# Microcontroller.net
KiCad netlist of a schematic drawn in Altium Designer
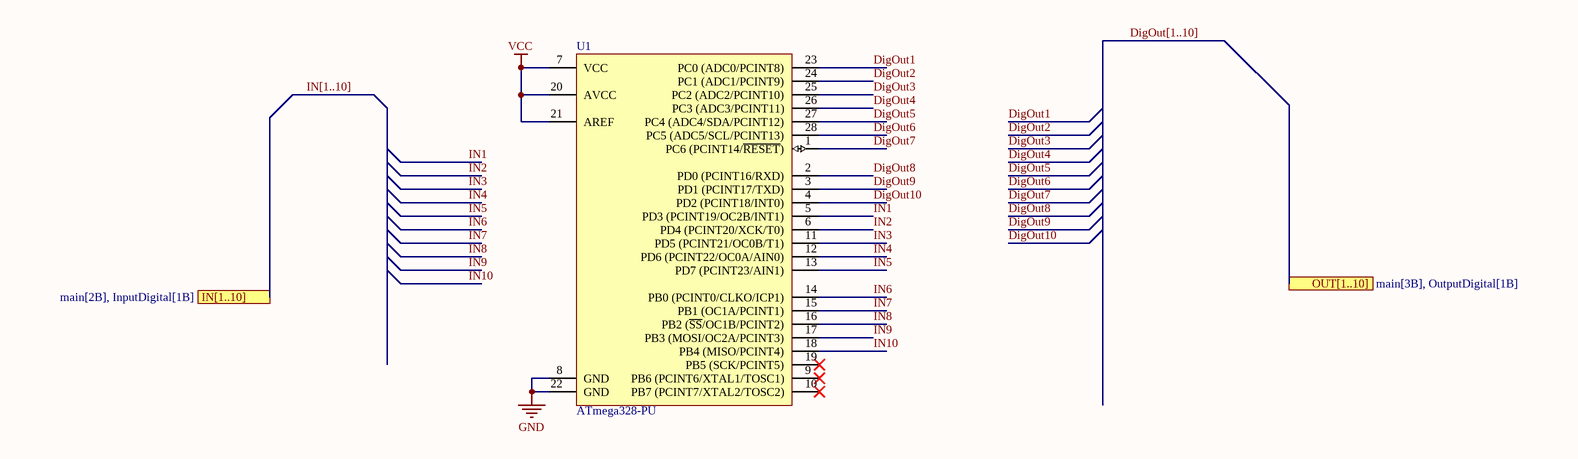
[diagram p0: Microcontroller.SchDoc]

(export (version "E")
  (design (tool "Eeschema 10.0.6"))
  (components
    (comp (ref "U1")
      (value "ATmega328-PU")
      (footprint "28P3")
      (libsource (lib "Ejemplo2") (part "CMP-0095-00015-2"))
    )
  )
  (nets
    (net (code "1") (name "/DigOut1") (class "Default")
      (node (ref "U1") (pin "23") (pinfunction "PC0_(ADC0/PCINT8)_23") (pintype "passive"))
    )
    (net (code "2") (name "/DigOut2") (class "Default")
      (node (ref "U1") (pin "24") (pinfunction "PC1_(ADC1/PCINT9)_24") (pintype "passive"))
    )
    (net (code "3") (name "/DigOut3") (class "Default")
      (node (ref "U1") (pin "25") (pinfunction "PC2_(ADC2/PCINT10)_25") (pintype "passive"))
    )
    (net (code "4") (name "/DigOut4") (class "Default")
      (node (ref "U1") (pin "26") (pinfunction "PC3_(ADC3/PCINT11)_26") (pintype "passive"))
    )
    (net (code "5") (name "/DigOut5") (class "Default")
      (node (ref "U1") (pin "27") (pinfunction "PC4_(ADC4/SDA/PCINT12)_27") (pintype "passive"))
    )
    (net (code "6") (name "/DigOut6") (class "Default")
      (node (ref "U1") (pin "28") (pinfunction "PC5_(ADC5/SCL/PCINT13)_28") (pintype "passive"))
    )
    (net (code "7") (name "/DigOut7") (class "Default")
      (node (ref "U1") (pin "1") (pinfunction "PC6_(PCINT14/~{RESET})_1") (pintype "bidirectional"))
    )
    (net (code "8") (name "/DigOut8") (class "Default")
      (node (ref "U1") (pin "2") (pinfunction "PD0_(PCINT16/RXD)_2") (pintype "passive"))
    )
    (net (code "9") (name "/DigOut9") (class "Default")
      (node (ref "U1") (pin "3") (pinfunction "PD1_(PCINT17/TXD)_3") (pintype "passive"))
    )
    (net (code "10") (name "/DigOut10") (class "Default")
      (node (ref "U1") (pin "4") (pinfunction "PD2_(PCINT18/INT0)_4") (pintype "passive"))
    )
    (net (code "12") (name "/IN1") (class "Default")
      (node (ref "U1") (pin "5") (pinfunction "PD3_(PCINT19/OC2B/INT1)_5") (pintype "passive"))
    )
    (net (code "13") (name "/IN2") (class "Default")
      (node (ref "U1") (pin "6") (pinfunction "PD4_(PCINT20/XCK/T0)_6") (pintype "passive"))
    )
    (net (code "14") (name "/IN3") (class "Default")
      (node (ref "U1") (pin "11") (pinfunction "PD5_(PCINT21/OC0B/T1)_11") (pintype "passive"))
    )
    (net (code "15") (name "/IN4") (class "Default")
      (node (ref "U1") (pin "12") (pinfunction "PD6_(PCINT22/OC0A/AIN0)_12") (pintype "passive"))
    )
    (net (code "16") (name "/IN5") (class "Default")
      (node (ref "U1") (pin "13") (pinfunction "PD7_(PCINT23/AIN1)_13") (pintype "passive"))
    )
    (net (code "17") (name "/IN6") (class "Default")
      (node (ref "U1") (pin "14") (pinfunction "PB0_(PCINT0/CLKO/ICP1)_14") (pintype "passive"))
    )
    (net (code "18") (name "/IN7") (class "Default")
      (node (ref "U1") (pin "15") (pinfunction "PB1_(OC1A/PCINT1)_15") (pintype "passive"))
    )
    (net (code "19") (name "/IN8") (class "Default")
      (node (ref "U1") (pin "16") (pinfunction "PB2_(~{SS}/OC1B/PCINT2)_16") (pintype "passive"))
    )
    (net (code "20") (name "/IN9") (class "Default")
      (node (ref "U1") (pin "17") (pinfunction "PB3_(MOSI/OC2A/PCINT3)_17") (pintype "passive"))
    )
    (net (code "21") (name "/IN10") (class "Default")
      (node (ref "U1") (pin "18") (pinfunction "PB4_(MISO/PCINT4)_18") (pintype "passive"))
    )
    (net (code "23") (name "GND") (class "Default")
      (node (ref "U1") (pin "22") (pinfunction "GND_22") (pintype "power_in"))
      (node (ref "U1") (pin "8") (pinfunction "GND_8") (pintype "power_in"))
    )
    (net (code "24") (name "VCC") (class "Default")
      (node (ref "U1") (pin "20") (pinfunction "AVCC_20") (pintype "power_in"))
      (node (ref "U1") (pin "21") (pinfunction "AREF_21") (pintype "power_in"))
      (node (ref "U1") (pin "7") (pinfunction "VCC_7") (pintype "power_in"))
    )
    (net (code "25") (name "unconnected-(U1-PB5_(SCK{slash}PCINT5)-Pad19)") (class "Default")
      (node (ref "U1") (pin "19") (pinfunction "PB5_(SCK/PCINT5)_19") (pintype "passive+no_connect"))
    )
    (net (code "26") (name "unconnected-(U1-PB6_(PCINT6{slash}XTAL1{slash}TOSC1)-Pad9)") (class "Default")
      (node (ref "U1") (pin "9") (pinfunction "PB6_(PCINT6/XTAL1/TOSC1)_9") (pintype "passive+no_connect"))
    )
    (net (code "27") (name "unconnected-(U1-PB7_(PCINT7{slash}XTAL2{slash}TOSC2)-Pad10)") (class "Default")
      (node (ref "U1") (pin "10") (pinfunction "PB7_(PCINT7/XTAL2/TOSC2)_10") (pintype "passive+no_connect"))
    )
  )
)
